# 3_STM32H750VBT6_schdoc.net
KiCad netlist of a schematic drawn in Altium Designer
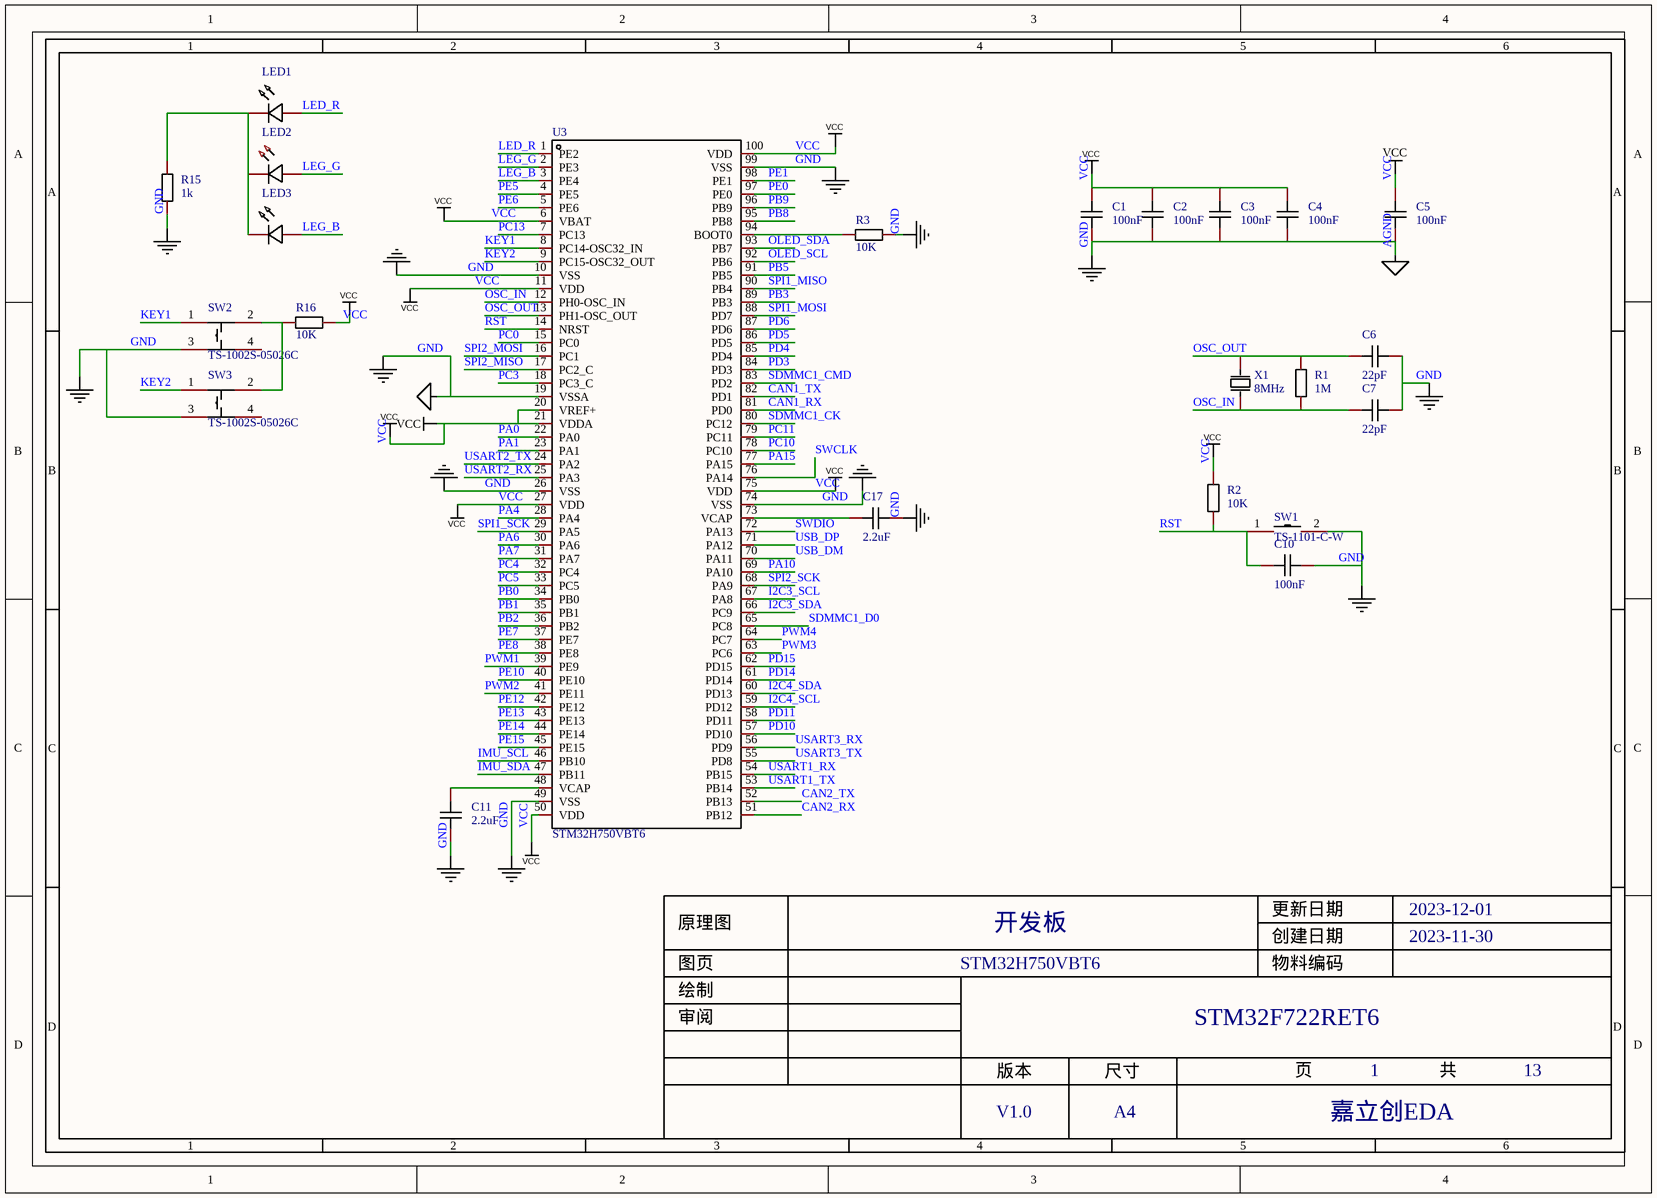
[diagram p0: 3_STM32H750VBT6.schdoc.schdoc]

(export (version "E")
  (design (tool "Eeschema 10.0.6"))
  (components
    (comp (ref "C1")
      (value "100nF")
      (fields (field (name "NAME") "100nF"))
      (libsource (lib "altium-import") (part "root_1_CAP_0805_"))
    )
    (comp (ref "C2")
      (value "100nF")
      (fields (field (name "NAME") "100nF"))
      (libsource (lib "altium-import") (part "root_1_CAP_0805_"))
    )
    (comp (ref "C3")
      (value "100nF")
      (fields (field (name "NAME") "100nF"))
      (libsource (lib "altium-import") (part "root_1_CAP_0805_"))
    )
    (comp (ref "C4")
      (value "100nF")
      (fields (field (name "NAME") "100nF"))
      (libsource (lib "altium-import") (part "root_1_CAP_0805_"))
    )
    (comp (ref "C5")
      (value "100nF")
      (fields (field (name "NAME") "100nF"))
      (libsource (lib "altium-import") (part "root_1_CAP_0805_"))
    )
    (comp (ref "C6")
      (value "22pF")
      (fields (field (name "NAME") "22pF"))
      (libsource (lib "altium-import") (part "root_0_CAP_0603_"))
    )
    (comp (ref "C7")
      (value "22pF")
      (fields (field (name "NAME") "22pF"))
      (libsource (lib "altium-import") (part "root_0_CAP_0603_"))
    )
    (comp (ref "C10")
      (value "100nF")
      (fields (field (name "NAME") "100nF"))
      (libsource (lib "altium-import") (part "root_0_CAP_0603_"))
    )
    (comp (ref "C11")
      (value "2.2uF")
      (fields (field (name "NAME") "2.2uF"))
      (libsource (lib "altium-import") (part "root_1_CAP_0603_"))
    )
    (comp (ref "C17")
      (value "2.2uF")
      (fields (field (name "NAME") "2.2uF"))
      (libsource (lib "altium-import") (part "root_2_CAP_0603_"))
    )
    (comp (ref "LED1")
      (value "LED_0603-R")
      (libsource (lib "altium-import") (part "root_0_mirrored_LED_0603-R_"))
    )
    (comp (ref "LED2")
      (value "LED_0603-G")
      (libsource (lib "altium-import") (part "root_0_mirrored_LED_0603-G_"))
    )
    (comp (ref "LED3")
      (value "LED_0603-B")
      (libsource (lib "altium-import") (part "root_0_mirrored_LED_0603-B_"))
    )
    (comp (ref "R1")
      (value "1M")
      (fields (field (name "NAME") "1M"))
      (libsource (lib "altium-import") (part "root_3_Res_0603_"))
    )
    (comp (ref "R2")
      (value "10K")
      (fields (field (name "NAME") "10K"))
      (libsource (lib "altium-import") (part "root_1_Res_0603_"))
    )
    (comp (ref "R3")
      (value "10K")
      (fields (field (name "NAME") "10K"))
      (libsource (lib "altium-import") (part "root_2_Res_0603_"))
    )
    (comp (ref "R15")
      (value "1k")
      (fields (field (name "NAME") "1k"))
      (libsource (lib "altium-import") (part "root_1_Res_0603_"))
    )
    (comp (ref "R16")
      (value "10K")
      (fields (field (name "NAME") "10K"))
      (libsource (lib "altium-import") (part "root_0_Res_0603_"))
    )
    (comp (ref "SW1")
      (value "TS-1101-C-W")
      (description "电路结构:单刀单掷;带支架:否;触点电流:50mA;额定电压(AC):-;额定电压(DC):12V;额定功率:-;安装方式:立贴;绝缘电阻:-;带灯:无;作用力:260gf;机械寿命:5万次;")
      (fields (field (name "NAME") "TS-1101-C-W") (field (name "MANUFACTURER") "XKB Connectivity(中国星坤)"))
      (libsource (lib "altium-import") (part "root_0_TS-1101-C-W_"))
    )
    (comp (ref "SW2")
      (value "TS-1002S-05026C")
      (description "电路结构:单刀单掷;触点电流:50mA;额定电压(DC):12V;安装方式:立贴;带灯:-;机械寿命:-;")
      (fields (field (name "NAME") "TS-1002S-05026C") (field (name "MANUFACTURER") "XUNPU(讯普)"))
      (libsource (lib "altium-import") (part "root_0_TS-1002S-05026C_"))
    )
    (comp (ref "SW3")
      (value "TS-1002S-05026C")
      (description "电路结构:单刀单掷;触点电流:50mA;额定电压(DC):12V;安装方式:立贴;带灯:-;机械寿命:-;")
      (fields (field (name "NAME") "TS-1002S-05026C") (field (name "MANUFACTURER") "XUNPU(讯普)"))
      (libsource (lib "altium-import") (part "root_0_TS-1002S-05026C_"))
    )
    (comp (ref "U3")
      (value "STM32H750VBT6")
      (description "CPU内核:ARM-M系列;CPU最大主频:480MHz;工作电压范围:1.62V~3.6V;程序存储容量:128KB;程序存储器类型:FLASH;RAM总容量:1MB;GPIO端口数量:82;")
      (fields (field (name "NAME") "STM32H750VBT6") (field (name "MANUFACTURER") "ST(意法半导体)"))
      (libsource (lib "altium-import") (part "root_0_STM32H750VBT6_"))
    )
    (comp (ref "X1")
      (value "8MHz")
      (description "频率:8MHz;负载电容:20pF;频率公差:±20ppm;")
      (fields
        (field (name "NAME") "8MHz")
        (field (name "MANUFACTURER") "YXC(扬兴晶振)")
        (field (name "MANUFACTURER PART") "X49SM8MSD2SC")
      )
      (libsource (lib "altium-import") (part "root_3_X49SM8MSD2SC_"))
    )
  )
  (nets
    (net (code "1") (name "/CAN1_RX") (class "Default")
      (node (ref "U3") (pin "81") (pinfunction "PD0_81") (pintype "passive"))
    )
    (net (code "2") (name "/CAN1_TX") (class "Default")
      (node (ref "U3") (pin "82") (pinfunction "PD1_82") (pintype "passive"))
    )
    (net (code "3") (name "/CAN2_RX") (class "Default")
      (node (ref "U3") (pin "51") (pinfunction "PB12_51") (pintype "passive"))
    )
    (net (code "4") (name "/CAN2_TX") (class "Default")
      (node (ref "U3") (pin "52") (pinfunction "PB13_52") (pintype "passive"))
    )
    (net (code "5") (name "/I2C3_SCL") (class "Default")
      (node (ref "U3") (pin "67") (pinfunction "PA8_67") (pintype "passive"))
    )
    (net (code "6") (name "/I2C3_SDA") (class "Default")
      (node (ref "U3") (pin "66") (pinfunction "PC9_66") (pintype "passive"))
    )
    (net (code "7") (name "/I2C4_SCL") (class "Default")
      (node (ref "U3") (pin "59") (pinfunction "PD12_59") (pintype "passive"))
    )
    (net (code "8") (name "/I2C4_SDA") (class "Default")
      (node (ref "U3") (pin "60") (pinfunction "PD13_60") (pintype "passive"))
    )
    (net (code "9") (name "/IMU_SCL") (class "Default")
      (node (ref "U3") (pin "46") (pinfunction "PB10_46") (pintype "passive"))
    )
    (net (code "10") (name "/IMU_SDA") (class "Default")
      (node (ref "U3") (pin "47") (pinfunction "PB11_47") (pintype "passive"))
    )
    (net (code "11") (name "/KEY1") (class "Default")
      (node (ref "SW2") (pin "1") (pinfunction "1_1") (pintype "passive"))
      (node (ref "U3") (pin "8") (pinfunction "PC14-OSC32_IN_8") (pintype "passive"))
    )
    (net (code "12") (name "/KEY2") (class "Default")
      (node (ref "SW3") (pin "1") (pinfunction "1_1") (pintype "passive"))
      (node (ref "U3") (pin "9") (pinfunction "PC15-OSC32_OUT_9") (pintype "passive"))
    )
    (net (code "13") (name "/LED_R") (class "Default")
      (node (ref "LED1") (pin "2") (pinfunction "A_2") (pintype "passive"))
      (node (ref "U3") (pin "1") (pinfunction "PE2_1") (pintype "passive"))
    )
    (net (code "14") (name "/LEG_B") (class "Default")
      (node (ref "LED3") (pin "2") (pinfunction "A_2") (pintype "passive"))
      (node (ref "U3") (pin "3") (pinfunction "PE4_3") (pintype "passive"))
    )
    (net (code "15") (name "/LEG_G") (class "Default")
      (node (ref "LED2") (pin "2") (pinfunction "A_2") (pintype "passive"))
      (node (ref "U3") (pin "2") (pinfunction "PE3_2") (pintype "passive"))
    )
    (net (code "16") (name "/OLED_SCL") (class "Default")
      (node (ref "U3") (pin "92") (pinfunction "PB6_92") (pintype "passive"))
    )
    (net (code "17") (name "/OLED_SDA") (class "Default")
      (node (ref "U3") (pin "93") (pinfunction "PB7_93") (pintype "passive"))
    )
    (net (code "18") (name "/OSC_IN") (class "Default")
      (node (ref "C7") (pin "1") (pinfunction "1_1") (pintype "passive"))
      (node (ref "R1") (pin "2") (pinfunction "2_2") (pintype "passive"))
      (node (ref "U3") (pin "12") (pinfunction "PH0-OSC_IN_12") (pintype "passive"))
      (node (ref "X1") (pin "1") (pinfunction "OSC1_1") (pintype "passive"))
    )
    (net (code "19") (name "/OSC_OUT") (class "Default")
      (node (ref "C6") (pin "1") (pinfunction "1_1") (pintype "passive"))
      (node (ref "R1") (pin "1") (pinfunction "1_1") (pintype "passive"))
      (node (ref "U3") (pin "13") (pinfunction "PH1-OSC_OUT_13") (pintype "passive"))
      (node (ref "X1") (pin "2") (pinfunction "OSC2_2") (pintype "passive"))
    )
    (net (code "20") (name "/PA0") (class "Default")
      (node (ref "U3") (pin "22") (pinfunction "PA0_22") (pintype "passive"))
    )
    (net (code "21") (name "/PA1") (class "Default")
      (node (ref "U3") (pin "23") (pinfunction "PA1_23") (pintype "passive"))
    )
    (net (code "22") (name "/PA4") (class "Default")
      (node (ref "U3") (pin "28") (pinfunction "PA4_28") (pintype "passive"))
    )
    (net (code "23") (name "/PA6") (class "Default")
      (node (ref "U3") (pin "30") (pinfunction "PA6_30") (pintype "passive"))
    )
    (net (code "24") (name "/PA7") (class "Default")
      (node (ref "U3") (pin "31") (pinfunction "PA7_31") (pintype "passive"))
    )
    (net (code "25") (name "/PA10") (class "Default")
      (node (ref "U3") (pin "69") (pinfunction "PA10_69") (pintype "passive"))
    )
    (net (code "26") (name "/PA15") (class "Default")
      (node (ref "U3") (pin "77") (pinfunction "PA15_77") (pintype "passive"))
    )
    (net (code "27") (name "/PB0") (class "Default")
      (node (ref "U3") (pin "34") (pinfunction "PB0_34") (pintype "passive"))
    )
    (net (code "28") (name "/PB1") (class "Default")
      (node (ref "U3") (pin "35") (pinfunction "PB1_35") (pintype "passive"))
    )
    (net (code "29") (name "/PB2") (class "Default")
      (node (ref "U3") (pin "36") (pinfunction "PB2_36") (pintype "passive"))
    )
    (net (code "30") (name "/PB3") (class "Default")
      (node (ref "U3") (pin "89") (pinfunction "PB3_89") (pintype "passive"))
    )
    (net (code "31") (name "/PB5") (class "Default")
      (node (ref "U3") (pin "91") (pinfunction "PB5_91") (pintype "passive"))
    )
    (net (code "32") (name "/PB8") (class "Default")
      (node (ref "U3") (pin "95") (pinfunction "PB8_95") (pintype "passive"))
    )
    (net (code "33") (name "/PB9") (class "Default")
      (node (ref "U3") (pin "96") (pinfunction "PB9_96") (pintype "passive"))
    )
    (net (code "34") (name "/PC0") (class "Default")
      (node (ref "U3") (pin "15") (pinfunction "PC0_15") (pintype "passive"))
    )
    (net (code "35") (name "/PC3") (class "Default")
      (node (ref "U3") (pin "18") (pinfunction "PC3_C_18") (pintype "passive"))
    )
    (net (code "36") (name "/PC4") (class "Default")
      (node (ref "U3") (pin "32") (pinfunction "PC4_32") (pintype "passive"))
    )
    (net (code "37") (name "/PC5") (class "Default")
      (node (ref "U3") (pin "33") (pinfunction "PC5_33") (pintype "passive"))
    )
    (net (code "38") (name "/PC10") (class "Default")
      (node (ref "U3") (pin "78") (pinfunction "PC10_78") (pintype "passive"))
    )
    (net (code "39") (name "/PC11") (class "Default")
      (node (ref "U3") (pin "79") (pinfunction "PC11_79") (pintype "passive"))
    )
    (net (code "40") (name "/PC13") (class "Default")
      (node (ref "U3") (pin "7") (pinfunction "PC13_7") (pintype "passive"))
    )
    (net (code "41") (name "/PD3") (class "Default")
      (node (ref "U3") (pin "84") (pinfunction "PD3_84") (pintype "passive"))
    )
    (net (code "42") (name "/PD4") (class "Default")
      (node (ref "U3") (pin "85") (pinfunction "PD4_85") (pintype "passive"))
    )
    (net (code "43") (name "/PD5") (class "Default")
      (node (ref "U3") (pin "86") (pinfunction "PD5_86") (pintype "passive"))
    )
    (net (code "44") (name "/PD6") (class "Default")
      (node (ref "U3") (pin "87") (pinfunction "PD6_87") (pintype "passive"))
    )
    (net (code "45") (name "/PD10") (class "Default")
      (node (ref "U3") (pin "57") (pinfunction "PD10_57") (pintype "passive"))
    )
    (net (code "46") (name "/PD11") (class "Default")
      (node (ref "U3") (pin "58") (pinfunction "PD11_58") (pintype "passive"))
    )
    (net (code "47") (name "/PD14") (class "Default")
      (node (ref "U3") (pin "61") (pinfunction "PD14_61") (pintype "passive"))
    )
    (net (code "48") (name "/PD15") (class "Default")
      (node (ref "U3") (pin "62") (pinfunction "PD15_62") (pintype "passive"))
    )
    (net (code "49") (name "/PE0") (class "Default")
      (node (ref "U3") (pin "97") (pinfunction "PE0_97") (pintype "passive"))
    )
    (net (code "50") (name "/PE1") (class "Default")
      (node (ref "U3") (pin "98") (pinfunction "PE1_98") (pintype "passive"))
    )
    (net (code "51") (name "/PE5") (class "Default")
      (node (ref "U3") (pin "4") (pinfunction "PE5_4") (pintype "passive"))
    )
    (net (code "52") (name "/PE6") (class "Default")
      (node (ref "U3") (pin "5") (pinfunction "PE6_5") (pintype "passive"))
    )
    (net (code "53") (name "/PE7") (class "Default")
      (node (ref "U3") (pin "37") (pinfunction "PE7_37") (pintype "passive"))
    )
    (net (code "54") (name "/PE8") (class "Default")
      (node (ref "U3") (pin "38") (pinfunction "PE8_38") (pintype "passive"))
    )
    (net (code "55") (name "/PE10") (class "Default")
      (node (ref "U3") (pin "40") (pinfunction "PE10_40") (pintype "passive"))
    )
    (net (code "56") (name "/PE12") (class "Default")
      (node (ref "U3") (pin "42") (pinfunction "PE12_42") (pintype "passive"))
    )
    (net (code "57") (name "/PE13") (class "Default")
      (node (ref "U3") (pin "43") (pinfunction "PE13_43") (pintype "passive"))
    )
    (net (code "58") (name "/PE14") (class "Default")
      (node (ref "U3") (pin "44") (pinfunction "PE14_44") (pintype "passive"))
    )
    (net (code "59") (name "/PE15") (class "Default")
      (node (ref "U3") (pin "45") (pinfunction "PE15_45") (pintype "passive"))
    )
    (net (code "60") (name "/PWM1") (class "Default")
      (node (ref "U3") (pin "39") (pinfunction "PE9_39") (pintype "passive"))
    )
    (net (code "61") (name "/PWM2") (class "Default")
      (node (ref "U3") (pin "41") (pinfunction "PE11_41") (pintype "passive"))
    )
    (net (code "62") (name "/PWM3") (class "Default")
      (node (ref "U3") (pin "63") (pinfunction "PC6_63") (pintype "passive"))
    )
    (net (code "63") (name "/PWM4") (class "Default")
      (node (ref "U3") (pin "64") (pinfunction "PC7_64") (pintype "passive"))
    )
    (net (code "64") (name "/RST") (class "Default")
      (node (ref "C10") (pin "1") (pinfunction "1_1") (pintype "passive"))
      (node (ref "R2") (pin "1") (pinfunction "1_1") (pintype "passive"))
      (node (ref "SW1") (pin "1") (pinfunction "1_1") (pintype "passive"))
      (node (ref "U3") (pin "14") (pinfunction "NRST_14") (pintype "passive"))
    )
    (net (code "65") (name "/SDMMC1_CK") (class "Default")
      (node (ref "U3") (pin "80") (pinfunction "PC12_80") (pintype "passive"))
    )
    (net (code "66") (name "/SDMMC1_CMD") (class "Default")
      (node (ref "U3") (pin "83") (pinfunction "PD2_83") (pintype "passive"))
    )
    (net (code "67") (name "/SDMMC1_D0") (class "Default")
      (node (ref "U3") (pin "65") (pinfunction "PC8_65") (pintype "passive"))
    )
    (net (code "68") (name "/SPI1_MISO") (class "Default")
      (node (ref "U3") (pin "90") (pinfunction "PB4_90") (pintype "passive"))
    )
    (net (code "69") (name "/SPI1_MOSI") (class "Default")
      (node (ref "U3") (pin "88") (pinfunction "PD7_88") (pintype "passive"))
    )
    (net (code "70") (name "/SPI1_SCK") (class "Default")
      (node (ref "U3") (pin "29") (pinfunction "PA5_29") (pintype "passive"))
    )
    (net (code "71") (name "/SPI2_MISO") (class "Default")
      (node (ref "U3") (pin "17") (pinfunction "PC2_C_17") (pintype "passive"))
    )
    (net (code "72") (name "/SPI2_MOSI") (class "Default")
      (node (ref "U3") (pin "16") (pinfunction "PC1_16") (pintype "passive"))
    )
    (net (code "73") (name "/SPI2_SCK") (class "Default")
      (node (ref "U3") (pin "68") (pinfunction "PA9_68") (pintype "passive"))
    )
    (net (code "74") (name "/SWCLK") (class "Default")
      (node (ref "U3") (pin "76") (pinfunction "PA14_76") (pintype "passive"))
    )
    (net (code "75") (name "/SWDIO") (class "Default")
      (node (ref "U3") (pin "72") (pinfunction "PA13_72") (pintype "passive"))
    )
    (net (code "76") (name "/USART1_RX") (class "Default")
      (node (ref "U3") (pin "54") (pinfunction "PB15_54") (pintype "passive"))
    )
    (net (code "77") (name "/USART1_TX") (class "Default")
      (node (ref "U3") (pin "53") (pinfunction "PB14_53") (pintype "passive"))
    )
    (net (code "78") (name "/USART2_RX") (class "Default")
      (node (ref "U3") (pin "25") (pinfunction "PA3_25") (pintype "passive"))
    )
    (net (code "79") (name "/USART2_TX") (class "Default")
      (node (ref "U3") (pin "24") (pinfunction "PA2_24") (pintype "passive"))
    )
    (net (code "80") (name "/USART3_RX") (class "Default")
      (node (ref "U3") (pin "56") (pinfunction "PD9_56") (pintype "passive"))
    )
    (net (code "81") (name "/USART3_TX") (class "Default")
      (node (ref "U3") (pin "55") (pinfunction "PD8_55") (pintype "passive"))
    )
    (net (code "82") (name "/USB_DM") (class "Default")
      (node (ref "U3") (pin "70") (pinfunction "PA11_70") (pintype "passive"))
    )
    (net (code "83") (name "/USB_DP") (class "Default")
      (node (ref "U3") (pin "71") (pinfunction "PA12_71") (pintype "passive"))
    )
    (net (code "84") (name "<NO NET>") (class "Default")
      (node (ref "C1") (pin "1") (pinfunction "1_1") (pintype "passive"))
      (node (ref "C10") (pin "2") (pinfunction "2_2") (pintype "passive"))
      (node (ref "C11") (pin "1") (pinfunction "1_1") (pintype "passive"))
      (node (ref "C17") (pin "1") (pinfunction "1_1") (pintype "passive"))
      (node (ref "C2") (pin "1") (pinfunction "1_1") (pintype "passive"))
      (node (ref "C3") (pin "1") (pinfunction "1_1") (pintype "passive"))
      (node (ref "C4") (pin "1") (pinfunction "1_1") (pintype "passive"))
      (node (ref "C5") (pin "1") (pinfunction "1_1") (pintype "passive"))
      (node (ref "C6") (pin "2") (pinfunction "2_2") (pintype "passive"))
      (node (ref "C7") (pin "2") (pinfunction "2_2") (pintype "passive"))
      (node (ref "R15") (pin "1") (pinfunction "1_1") (pintype "passive"))
      (node (ref "R3") (pin "1") (pinfunction "1_1") (pintype "passive"))
      (node (ref "SW1") (pin "2") (pinfunction "2_2") (pintype "passive"))
      (node (ref "SW2") (pin "3") (pinfunction "3_3") (pintype "passive"))
      (node (ref "SW3") (pin "3") (pinfunction "3_3") (pintype "passive"))
      (node (ref "U3") (pin "10") (pinfunction "VSS_10") (pintype "passive"))
      (node (ref "U3") (pin "19") (pinfunction "VSSA_19") (pintype "passive"))
      (node (ref "U3") (pin "26") (pinfunction "VSS_26") (pintype "passive"))
      (node (ref "U3") (pin "49") (pinfunction "VSS_49") (pintype "passive"))
      (node (ref "U3") (pin "74") (pinfunction "VSS_74") (pintype "passive"))
      (node (ref "U3") (pin "99") (pinfunction "VSS_99") (pintype "passive"))
    )
    (net (code "85") (name "Net-(C11-Pad2)") (class "Default")
      (node (ref "C11") (pin "2") (pinfunction "2_2") (pintype "passive"))
      (node (ref "U3") (pin "48") (pinfunction "VCAP_48") (pintype "passive"))
    )
    (net (code "86") (name "Net-(C17-Pad2)") (class "Default")
      (node (ref "C17") (pin "2") (pinfunction "2_2") (pintype "passive"))
      (node (ref "U3") (pin "73") (pinfunction "VCAP_73") (pintype "passive"))
    )
    (net (code "87") (name "Net-(LED1-C)") (class "Default")
      (node (ref "LED1") (pin "1") (pinfunction "C_1") (pintype "passive"))
      (node (ref "LED2") (pin "1") (pinfunction "C_1") (pintype "passive"))
      (node (ref "LED3") (pin "1") (pinfunction "C_1") (pintype "passive"))
      (node (ref "R15") (pin "2") (pinfunction "2_2") (pintype "passive"))
    )
    (net (code "88") (name "Net-(R16-Pad1)") (class "Default")
      (node (ref "R16") (pin "1") (pinfunction "1_1") (pintype "passive"))
      (node (ref "SW2") (pin "2") (pinfunction "2_2") (pintype "passive"))
      (node (ref "SW3") (pin "2") (pinfunction "2_2") (pintype "passive"))
    )
    (net (code "89") (name "Net-(U3-BOOT0)") (class "Default")
      (node (ref "R3") (pin "2") (pinfunction "2_2") (pintype "passive"))
      (node (ref "U3") (pin "94") (pinfunction "BOOT0_94") (pintype "passive"))
    )
    (net (code "90") (name "VCC") (class "Default")
      (node (ref "C1") (pin "2") (pinfunction "2_2") (pintype "passive"))
      (node (ref "C2") (pin "2") (pinfunction "2_2") (pintype "passive"))
      (node (ref "C3") (pin "2") (pinfunction "2_2") (pintype "passive"))
      (node (ref "C4") (pin "2") (pinfunction "2_2") (pintype "passive"))
      (node (ref "C5") (pin "2") (pinfunction "2_2") (pintype "passive"))
      (node (ref "R16") (pin "2") (pinfunction "2_2") (pintype "passive"))
      (node (ref "R2") (pin "2") (pinfunction "2_2") (pintype "passive"))
      (node (ref "U3") (pin "100") (pinfunction "VDD_100") (pintype "passive"))
      (node (ref "U3") (pin "11") (pinfunction "VDD_11") (pintype "passive"))
      (node (ref "U3") (pin "20") (pinfunction "VREF+_20") (pintype "passive"))
      (node (ref "U3") (pin "21") (pinfunction "VDDA_21") (pintype "passive"))
      (node (ref "U3") (pin "27") (pinfunction "VDD_27") (pintype "passive"))
      (node (ref "U3") (pin "50") (pinfunction "VDD_50") (pintype "passive"))
      (node (ref "U3") (pin "6") (pinfunction "VBAT_6") (pintype "passive"))
      (node (ref "U3") (pin "75") (pinfunction "VDD_75") (pintype "passive"))
    )
    (net (code "91") (name "unconnected-(SW2-Pad4)") (class "Default")
      (node (ref "SW2") (pin "4") (pinfunction "4_4") (pintype "passive"))
    )
    (net (code "92") (name "unconnected-(SW3-Pad4)") (class "Default")
      (node (ref "SW3") (pin "4") (pinfunction "4_4") (pintype "passive"))
    )
  )
)
